# ProPrj_51__2025-02-26.net
KiCad netlist of a schematic drawn in EasyEDA Pro
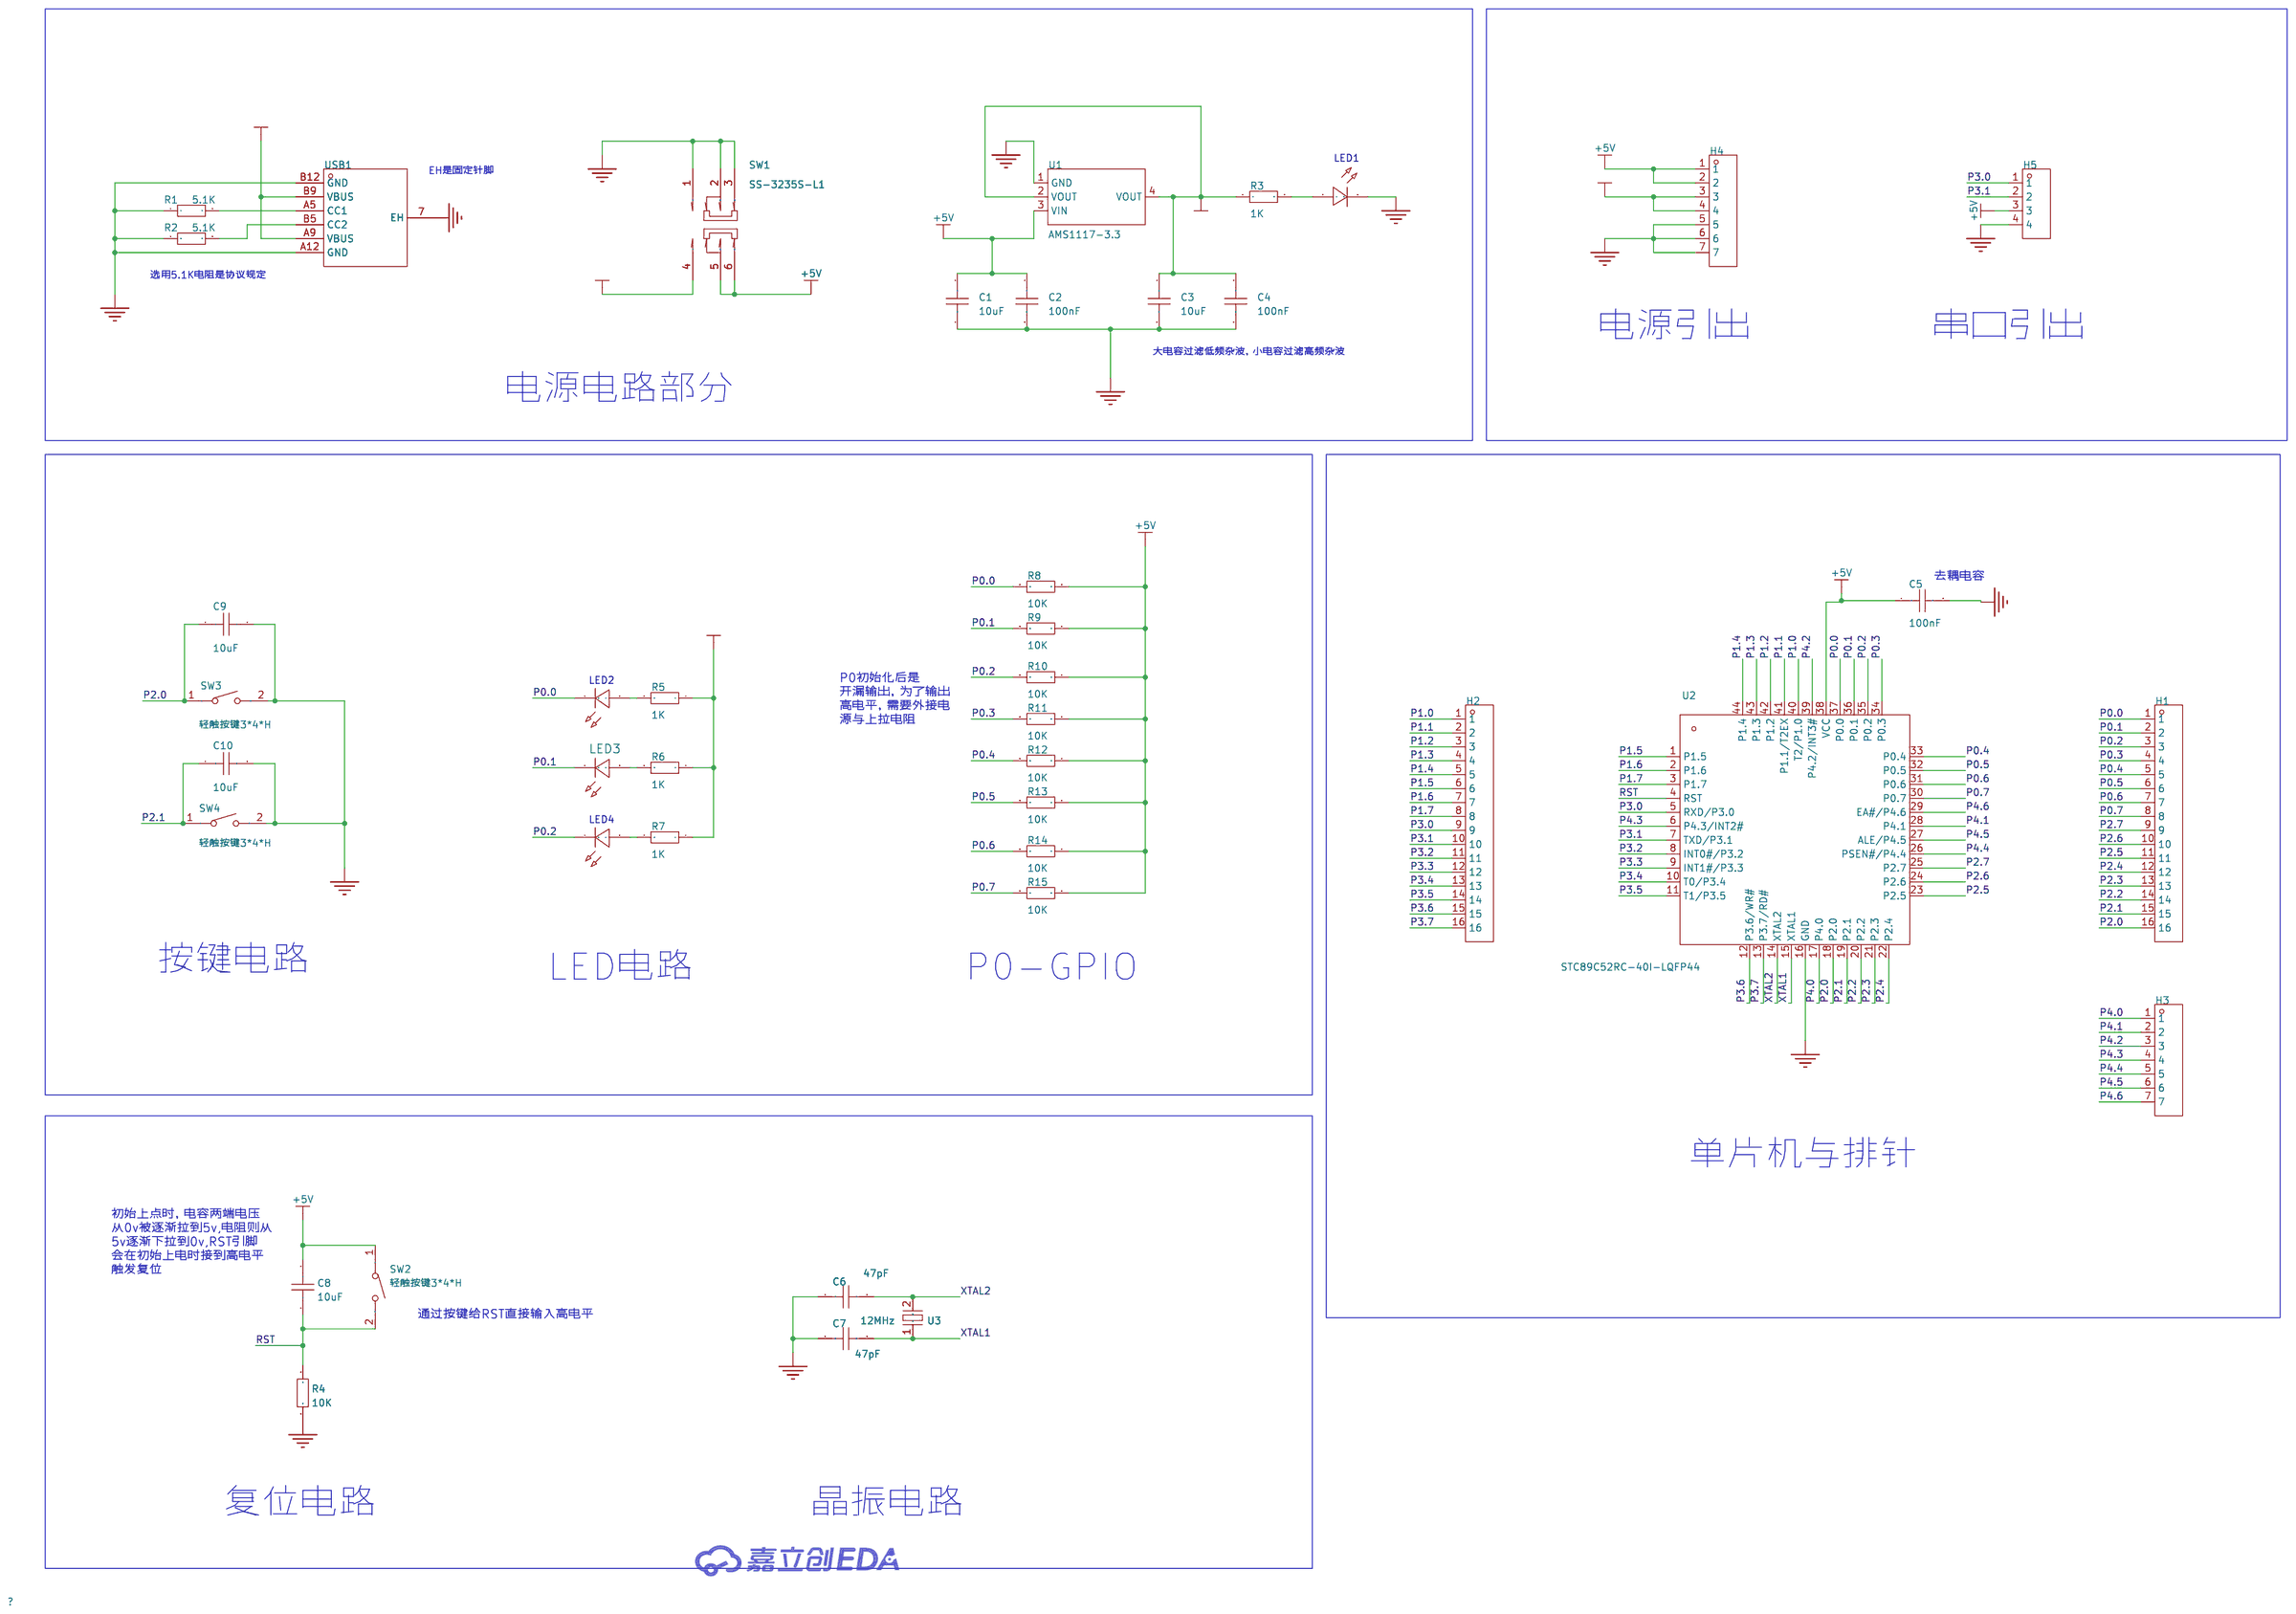
[diagram p0: schematic sheet]

(export (version "E")
  (design (tool "Eeschema 10.0.6"))
  (components
    (comp (ref "C1")
      (value "10uF")
      (footprint "easyedapro:C0805")
      (libsource (lib "easyedapro") (part "CapAcitance"))
    )
    (comp (ref "C2")
      (value "100nF")
      (footprint "easyedapro:C0805")
      (libsource (lib "easyedapro") (part "CapAcitance"))
    )
    (comp (ref "C3")
      (value "10uF")
      (footprint "easyedapro:C0805")
      (libsource (lib "easyedapro") (part "CapAcitance"))
    )
    (comp (ref "C4")
      (value "100nF")
      (footprint "easyedapro:C0805")
      (libsource (lib "easyedapro") (part "CapAcitance"))
    )
    (comp (ref "C5")
      (value "100nF")
      (footprint "easyedapro:C0805")
      (libsource (lib "easyedapro") (part "CapAcitance"))
    )
    (comp (ref "C6")
      (value "47pF")
      (footprint "easyedapro:C0805")
      (libsource (lib "easyedapro") (part "CapAcitance"))
    )
    (comp (ref "C7")
      (value "47pF")
      (footprint "easyedapro:C0805")
      (libsource (lib "easyedapro") (part "CapAcitance"))
    )
    (comp (ref "C8")
      (value "10uF")
      (footprint "easyedapro:C0805")
      (libsource (lib "easyedapro") (part "CapAcitance"))
    )
    (comp (ref "C9")
      (value "10uF")
      (footprint "easyedapro:C0805")
      (libsource (lib "easyedapro") (part "CapAcitance"))
    )
    (comp (ref "C10")
      (value "10uF")
      (footprint "easyedapro:C0805")
      (libsource (lib "easyedapro") (part "CapAcitance"))
    )
    (comp (ref "H1")
      (value "~")
      (footprint "easyedapro:HDR-TH_16P-P2.54-V-M")
      (libsource (lib "easyedapro") (part "HDR_2.54-1x16P"))
    )
    (comp (ref "H2")
      (value "~")
      (footprint "easyedapro:HDR-TH_16P-P2.54-V-M")
      (libsource (lib "easyedapro") (part "HDR_2.54-1x16P"))
    )
    (comp (ref "H3")
      (value "~")
      (footprint "easyedapro:HDR-TH_7P-P2.54-V-M")
      (libsource (lib "easyedapro") (part "PZ254V-11-07P"))
    )
    (comp (ref "H4")
      (value "~")
      (footprint "easyedapro:HDR-TH_7P-P2.54-V-M")
      (libsource (lib "easyedapro") (part "PZ254V-11-07P"))
    )
    (comp (ref "H5")
      (value "~")
      (footprint "easyedapro:HDR-TH_4P-P2.54-V-M")
      (libsource (lib "easyedapro") (part "PZ254V-11-04P"))
    )
    (comp (ref "LED1")
      (value "~")
      (footprint "easyedapro:LED_0805")
      (libsource (lib "easyedapro") (part "LED_G"))
    )
    (comp (ref "LED2")
      (value "~")
      (footprint "easyedapro:LED_0805")
      (libsource (lib "easyedapro") (part "LED_G"))
    )
    (comp (ref "LED3")
      (value "~")
      (footprint "easyedapro:LED_0805")
      (libsource (lib "easyedapro") (part "LED_R"))
    )
    (comp (ref "LED4")
      (value "~")
      (footprint "easyedapro:LED_0805")
      (libsource (lib "easyedapro") (part "LED_B"))
    )
    (comp (ref "R1") (value "5.1K") (footprint "easyedapro:R0805") (libsource (lib "easyedapro") (part "电阻")))
    (comp (ref "R2") (value "5.1K") (footprint "easyedapro:R0805") (libsource (lib "easyedapro") (part "电阻")))
    (comp (ref "R3") (value "1K") (footprint "easyedapro:R0805") (libsource (lib "easyedapro") (part "电阻")))
    (comp (ref "R4") (value "10K") (footprint "easyedapro:R0805") (libsource (lib "easyedapro") (part "电阻")))
    (comp (ref "R5") (value "1K") (footprint "easyedapro:R0805") (libsource (lib "easyedapro") (part "电阻")))
    (comp (ref "R6") (value "1K") (footprint "easyedapro:R0805") (libsource (lib "easyedapro") (part "电阻")))
    (comp (ref "R7") (value "1K") (footprint "easyedapro:R0805") (libsource (lib "easyedapro") (part "电阻")))
    (comp (ref "R8") (value "10K") (footprint "easyedapro:R0805") (libsource (lib "easyedapro") (part "电阻")))
    (comp (ref "R9") (value "10K") (footprint "easyedapro:R0805") (libsource (lib "easyedapro") (part "电阻")))
    (comp (ref "R10") (value "10K") (footprint "easyedapro:R0805") (libsource (lib "easyedapro") (part "电阻")))
    (comp (ref "R11") (value "10K") (footprint "easyedapro:R0805") (libsource (lib "easyedapro") (part "电阻")))
    (comp (ref "R12") (value "10K") (footprint "easyedapro:R0805") (libsource (lib "easyedapro") (part "电阻")))
    (comp (ref "R13") (value "10K") (footprint "easyedapro:R0805") (libsource (lib "easyedapro") (part "电阻")))
    (comp (ref "R14") (value "10K") (footprint "easyedapro:R0805") (libsource (lib "easyedapro") (part "电阻")))
    (comp (ref "R15") (value "10K") (footprint "easyedapro:R0805") (libsource (lib "easyedapro") (part "电阻")))
    (comp (ref "SW1")
      (value "SS-3235S-L1")
      (footprint "easyedapro:SW-SMD_SS-3235S-LX")
      (description "电路结构:双刀双掷;安装方式:卧贴;开关颜色:黑色;额定电流(DC):50mA;额定电压(DC):12V;额定电流(AC):50mA;额定电压(AC):12V;机械寿命:1万次;")
      (fields (field (name "Manufacturer") "XKB Connectivity(中国星坤)"))
      (libsource (lib "easyedapro") (part "SS-3235S-L1"))
    )
    (comp (ref "SW2")
      (value "轻触按键3*4*H")
      (footprint "easyedapro:SW-SMD_L4.0-W2.9-LS5.0")
      (libsource (lib "easyedapro") (part "轻触按键3*4*H"))
    )
    (comp (ref "SW3")
      (value "轻触按键3*4*H")
      (footprint "easyedapro:SW-SMD_L4.0-W2.9-LS5.0")
      (libsource (lib "easyedapro") (part "轻触按键3*4*H"))
    )
    (comp (ref "SW4")
      (value "轻触按键3*4*H")
      (footprint "easyedapro:SW-SMD_L4.0-W2.9-LS5.0")
      (libsource (lib "easyedapro") (part "轻触按键3*4*H"))
    )
    (comp (ref "U1")
      (value "AMS1117-3.3")
      (footprint "easyedapro:SOT-223-3_L6.5-W3.4-P2.30-LS7.0-BR")
      (description "输出类型:固定;工作电压:-;输出电压:3.3V;输出电流:1A;电源纹波抑制比(PSRR):72dB@(120Hz);输出极性:正极;")
      (fields (field (name "Manufacturer") "AMS"))
      (libsource (lib "easyedapro") (part "AMS1117-3.3"))
    )
    (comp (ref "U2")
      (value "STC89C52RC-40I-LQFP44")
      (footprint "easyedapro:LQFP-44_L10.0-W10.0-P0.80-LS12.0-BL")
      (description "CPU内核:51系列;应用领域:-;")
      (fields (field (name "Manufacturer") "STC"))
      (libsource (lib "easyedapro") (part "STC89C52RC-40I_C8707"))
    )
    (comp (ref "U3")
      (value "12MHz")
      (footprint "easyedapro:CRYSTAL-SMD_L11.4-W4.7-LS12.7")
      (description "频率:12MHz;常温频差:±30ppm;外接负载电容:18pF;频率稳定度(全温):±35ppm;")
      (fields
        (field (name "Manufacturer Part") "ABLS-12.000MHZ-B4H-T")
        (field (name "Manufacturer") "ABRACON")
      )
      (libsource (lib "easyedapro") (part "ABLS-12.000MHZ-B4H-T"))
    )
    (comp (ref "USB1")
      (value "TYPE-C-6P-DIP2X2")
      (footprint "easyedapro:TYPE-C-SMD_TYPE-C-6P")
      (libsource (lib "easyedapro") (part "TYPE-C-6P-DIP2X2"))
    )
  )
  (nets
    (net (code "1") (name "+3.3V") (class "Default")
      (node (ref "C3") (pin "1") (pinfunction "1_1") (pintype "input"))
      (node (ref "C4") (pin "1") (pinfunction "1_1") (pintype "input"))
      (node (ref "H4") (pin "3") (pinfunction "3_3") (pintype "unspecified"))
      (node (ref "H4") (pin "4") (pinfunction "4_4") (pintype "unspecified"))
      (node (ref "R3") (pin "1") (pinfunction "1_1") (pintype "input"))
      (node (ref "R5") (pin "1") (pinfunction "1_1") (pintype "input"))
      (node (ref "R6") (pin "1") (pinfunction "1_1") (pintype "input"))
      (node (ref "R7") (pin "1") (pinfunction "1_1") (pintype "input"))
      (node (ref "U1") (pin "2") (pinfunction "VOUT_2") (pintype "unspecified"))
      (node (ref "U1") (pin "4") (pinfunction "VOUT_4") (pintype "unspecified"))
    )
    (net (code "2") (name "+5V") (class "Default")
      (node (ref "C1") (pin "1") (pinfunction "1_1") (pintype "input"))
      (node (ref "C2") (pin "1") (pinfunction "1_1") (pintype "input"))
      (node (ref "C5") (pin "1") (pinfunction "1_1") (pintype "input"))
      (node (ref "C8") (pin "2") (pinfunction "2_2") (pintype "input"))
      (node (ref "H4") (pin "1") (pinfunction "1_1") (pintype "unspecified"))
      (node (ref "H4") (pin "2") (pinfunction "2_2") (pintype "unspecified"))
      (node (ref "H5") (pin "3") (pinfunction "3_3") (pintype "unspecified"))
      (node (ref "R10") (pin "1") (pinfunction "1_1") (pintype "input"))
      (node (ref "R11") (pin "1") (pinfunction "1_1") (pintype "input"))
      (node (ref "R12") (pin "1") (pinfunction "1_1") (pintype "input"))
      (node (ref "R13") (pin "1") (pinfunction "1_1") (pintype "input"))
      (node (ref "R14") (pin "1") (pinfunction "1_1") (pintype "input"))
      (node (ref "R15") (pin "1") (pinfunction "1_1") (pintype "input"))
      (node (ref "R8") (pin "1") (pinfunction "1_1") (pintype "input"))
      (node (ref "R9") (pin "1") (pinfunction "1_1") (pintype "input"))
      (node (ref "SW1") (pin "5") (pinfunction "5_5") (pintype "unspecified"))
      (node (ref "SW1") (pin "6") (pinfunction "6_6") (pintype "unspecified"))
      (node (ref "SW2") (pin "1") (pinfunction "1_1") (pintype "unspecified"))
      (node (ref "U1") (pin "3") (pinfunction "VIN_3") (pintype "unspecified"))
      (node (ref "U2") (pin "38") (pinfunction "VCC_38") (pintype "unspecified"))
    )
    (net (code "3") (name "/P0.0") (class "Default")
      (node (ref "H1") (pin "1") (pinfunction "1_1") (pintype "input"))
      (node (ref "LED2") (pin "1") (pinfunction "C_1") (pintype "input"))
      (node (ref "R8") (pin "2") (pinfunction "2_2") (pintype "input"))
      (node (ref "U2") (pin "37") (pinfunction "P0.0_37") (pintype "unspecified"))
    )
    (net (code "4") (name "/P0.1") (class "Default")
      (node (ref "H1") (pin "2") (pinfunction "2_2") (pintype "input"))
      (node (ref "LED3") (pin "1") (pinfunction "C_1") (pintype "input"))
      (node (ref "R9") (pin "2") (pinfunction "2_2") (pintype "input"))
      (node (ref "U2") (pin "36") (pinfunction "P0.1_36") (pintype "unspecified"))
    )
    (net (code "5") (name "/P0.2") (class "Default")
      (node (ref "H1") (pin "3") (pinfunction "3_3") (pintype "input"))
      (node (ref "LED4") (pin "1") (pinfunction "C_1") (pintype "input"))
      (node (ref "R10") (pin "2") (pinfunction "2_2") (pintype "input"))
      (node (ref "U2") (pin "35") (pinfunction "P0.2_35") (pintype "unspecified"))
    )
    (net (code "6") (name "/P0.3") (class "Default")
      (node (ref "H1") (pin "4") (pinfunction "4_4") (pintype "input"))
      (node (ref "R11") (pin "2") (pinfunction "2_2") (pintype "input"))
      (node (ref "U2") (pin "34") (pinfunction "P0.3_34") (pintype "unspecified"))
    )
    (net (code "7") (name "/P0.4") (class "Default")
      (node (ref "H1") (pin "5") (pinfunction "5_5") (pintype "input"))
      (node (ref "R12") (pin "2") (pinfunction "2_2") (pintype "input"))
      (node (ref "U2") (pin "33") (pinfunction "P0.4_33") (pintype "unspecified"))
    )
    (net (code "8") (name "/P0.5") (class "Default")
      (node (ref "H1") (pin "6") (pinfunction "6_6") (pintype "input"))
      (node (ref "R13") (pin "2") (pinfunction "2_2") (pintype "input"))
      (node (ref "U2") (pin "32") (pinfunction "P0.5_32") (pintype "unspecified"))
    )
    (net (code "9") (name "/P0.6") (class "Default")
      (node (ref "H1") (pin "7") (pinfunction "7_7") (pintype "input"))
      (node (ref "R14") (pin "2") (pinfunction "2_2") (pintype "input"))
      (node (ref "U2") (pin "31") (pinfunction "P0.6_31") (pintype "unspecified"))
    )
    (net (code "10") (name "/P0.7") (class "Default")
      (node (ref "H1") (pin "8") (pinfunction "8_8") (pintype "input"))
      (node (ref "R15") (pin "2") (pinfunction "2_2") (pintype "input"))
      (node (ref "U2") (pin "30") (pinfunction "P0.7_30") (pintype "unspecified"))
    )
    (net (code "11") (name "/P1.0") (class "Default")
      (node (ref "H2") (pin "1") (pinfunction "1_1") (pintype "input"))
      (node (ref "U2") (pin "40") (pinfunction "T2/P1.0_40") (pintype "unspecified"))
    )
    (net (code "12") (name "/P1.1") (class "Default")
      (node (ref "H2") (pin "2") (pinfunction "2_2") (pintype "input"))
      (node (ref "U2") (pin "41") (pinfunction "P1.1/T2EX_41") (pintype "unspecified"))
    )
    (net (code "13") (name "/P1.2") (class "Default")
      (node (ref "H2") (pin "3") (pinfunction "3_3") (pintype "input"))
      (node (ref "U2") (pin "42") (pinfunction "P1.2_42") (pintype "unspecified"))
    )
    (net (code "14") (name "/P1.3") (class "Default")
      (node (ref "H2") (pin "4") (pinfunction "4_4") (pintype "input"))
      (node (ref "U2") (pin "43") (pinfunction "P1.3_43") (pintype "unspecified"))
    )
    (net (code "15") (name "/P1.4") (class "Default")
      (node (ref "H2") (pin "5") (pinfunction "5_5") (pintype "input"))
      (node (ref "U2") (pin "44") (pinfunction "P1.4_44") (pintype "unspecified"))
    )
    (net (code "16") (name "/P1.5") (class "Default")
      (node (ref "H2") (pin "6") (pinfunction "6_6") (pintype "input"))
      (node (ref "U2") (pin "1") (pinfunction "P1.5_1") (pintype "unspecified"))
    )
    (net (code "17") (name "/P1.6") (class "Default")
      (node (ref "H2") (pin "7") (pinfunction "7_7") (pintype "input"))
      (node (ref "U2") (pin "2") (pinfunction "P1.6_2") (pintype "unspecified"))
    )
    (net (code "18") (name "/P1.7") (class "Default")
      (node (ref "H2") (pin "8") (pinfunction "8_8") (pintype "input"))
      (node (ref "U2") (pin "3") (pinfunction "P1.7_3") (pintype "unspecified"))
    )
    (net (code "19") (name "/P2.0") (class "Default")
      (node (ref "C9") (pin "1") (pinfunction "1_1") (pintype "input"))
      (node (ref "H1") (pin "16") (pinfunction "16_16") (pintype "input"))
      (node (ref "SW3") (pin "1") (pinfunction "1_1") (pintype "unspecified"))
      (node (ref "U2") (pin "18") (pinfunction "P2.0_18") (pintype "unspecified"))
    )
    (net (code "20") (name "/P2.1") (class "Default")
      (node (ref "C10") (pin "1") (pinfunction "1_1") (pintype "input"))
      (node (ref "H1") (pin "15") (pinfunction "15_15") (pintype "input"))
      (node (ref "SW4") (pin "1") (pinfunction "1_1") (pintype "unspecified"))
      (node (ref "U2") (pin "19") (pinfunction "P2.1_19") (pintype "unspecified"))
    )
    (net (code "21") (name "/P2.2") (class "Default")
      (node (ref "H1") (pin "14") (pinfunction "14_14") (pintype "input"))
      (node (ref "U2") (pin "20") (pinfunction "P2.2_20") (pintype "unspecified"))
    )
    (net (code "22") (name "/P2.3") (class "Default")
      (node (ref "H1") (pin "13") (pinfunction "13_13") (pintype "input"))
      (node (ref "U2") (pin "21") (pinfunction "P2.3_21") (pintype "unspecified"))
    )
    (net (code "23") (name "/P2.4") (class "Default")
      (node (ref "H1") (pin "12") (pinfunction "12_12") (pintype "input"))
      (node (ref "U2") (pin "22") (pinfunction "P2.4_22") (pintype "unspecified"))
    )
    (net (code "24") (name "/P2.5") (class "Default")
      (node (ref "H1") (pin "11") (pinfunction "11_11") (pintype "input"))
      (node (ref "U2") (pin "23") (pinfunction "P2.5_23") (pintype "unspecified"))
    )
    (net (code "25") (name "/P2.6") (class "Default")
      (node (ref "H1") (pin "10") (pinfunction "10_10") (pintype "input"))
      (node (ref "U2") (pin "24") (pinfunction "P2.6_24") (pintype "unspecified"))
    )
    (net (code "26") (name "/P2.7") (class "Default")
      (node (ref "H1") (pin "9") (pinfunction "9_9") (pintype "input"))
      (node (ref "U2") (pin "25") (pinfunction "P2.7_25") (pintype "unspecified"))
    )
    (net (code "27") (name "/P3.0") (class "Default")
      (node (ref "H2") (pin "9") (pinfunction "9_9") (pintype "input"))
      (node (ref "H5") (pin "1") (pinfunction "1_1") (pintype "unspecified"))
      (node (ref "U2") (pin "5") (pinfunction "RXD/P3.0_5") (pintype "unspecified"))
    )
    (net (code "28") (name "/P3.1") (class "Default")
      (node (ref "H2") (pin "10") (pinfunction "10_10") (pintype "input"))
      (node (ref "H5") (pin "2") (pinfunction "2_2") (pintype "unspecified"))
      (node (ref "U2") (pin "7") (pinfunction "TXD/P3.1_7") (pintype "unspecified"))
    )
    (net (code "29") (name "/P3.2") (class "Default")
      (node (ref "H2") (pin "11") (pinfunction "11_11") (pintype "input"))
      (node (ref "U2") (pin "8") (pinfunction "INT0#/P3.2_8") (pintype "unspecified"))
    )
    (net (code "30") (name "/P3.3") (class "Default")
      (node (ref "H2") (pin "12") (pinfunction "12_12") (pintype "input"))
      (node (ref "U2") (pin "9") (pinfunction "INT1#/P3.3_9") (pintype "unspecified"))
    )
    (net (code "31") (name "/P3.4") (class "Default")
      (node (ref "H2") (pin "13") (pinfunction "13_13") (pintype "input"))
      (node (ref "U2") (pin "10") (pinfunction "T0/P3.4_10") (pintype "unspecified"))
    )
    (net (code "32") (name "/P3.5") (class "Default")
      (node (ref "H2") (pin "14") (pinfunction "14_14") (pintype "input"))
      (node (ref "U2") (pin "11") (pinfunction "T1/P3.5_11") (pintype "unspecified"))
    )
    (net (code "33") (name "/P3.6") (class "Default")
      (node (ref "H2") (pin "15") (pinfunction "15_15") (pintype "input"))
      (node (ref "U2") (pin "12") (pinfunction "P3.6/WR#_12") (pintype "unspecified"))
    )
    (net (code "34") (name "/P3.7") (class "Default")
      (node (ref "H2") (pin "16") (pinfunction "16_16") (pintype "input"))
      (node (ref "U2") (pin "13") (pinfunction "P3.7/RD#_13") (pintype "unspecified"))
    )
    (net (code "35") (name "/P4.0") (class "Default")
      (node (ref "H3") (pin "1") (pinfunction "1_1") (pintype "unspecified"))
      (node (ref "U2") (pin "17") (pinfunction "P4.0_17") (pintype "unspecified"))
    )
    (net (code "36") (name "/P4.1") (class "Default")
      (node (ref "H3") (pin "2") (pinfunction "2_2") (pintype "unspecified"))
      (node (ref "U2") (pin "28") (pinfunction "P4.1_28") (pintype "unspecified"))
    )
    (net (code "37") (name "/P4.2") (class "Default")
      (node (ref "H3") (pin "3") (pinfunction "3_3") (pintype "unspecified"))
      (node (ref "U2") (pin "39") (pinfunction "P4.2/INT3#_39") (pintype "unspecified"))
    )
    (net (code "38") (name "/P4.3") (class "Default")
      (node (ref "H3") (pin "4") (pinfunction "4_4") (pintype "unspecified"))
      (node (ref "U2") (pin "6") (pinfunction "P4.3/INT2#_6") (pintype "unspecified"))
    )
    (net (code "39") (name "/P4.4") (class "Default")
      (node (ref "H3") (pin "5") (pinfunction "5_5") (pintype "unspecified"))
      (node (ref "U2") (pin "26") (pinfunction "PSEN#/P4.4_26") (pintype "unspecified"))
    )
    (net (code "40") (name "/P4.5") (class "Default")
      (node (ref "H3") (pin "6") (pinfunction "6_6") (pintype "unspecified"))
      (node (ref "U2") (pin "27") (pinfunction "ALE/P4.5_27") (pintype "unspecified"))
    )
    (net (code "41") (name "/P4.6") (class "Default")
      (node (ref "H3") (pin "7") (pinfunction "7_7") (pintype "unspecified"))
      (node (ref "U2") (pin "29") (pinfunction "EA#/P4.6_29") (pintype "unspecified"))
    )
    (net (code "42") (name "/RST") (class "Default")
      (node (ref "C8") (pin "1") (pinfunction "1_1") (pintype "input"))
      (node (ref "R4") (pin "2") (pinfunction "2_2") (pintype "input"))
      (node (ref "SW2") (pin "2") (pinfunction "2_2") (pintype "unspecified"))
      (node (ref "U2") (pin "4") (pinfunction "RST_4") (pintype "unspecified"))
    )
    (net (code "43") (name "/XTAL1") (class "Default")
      (node (ref "C7") (pin "2") (pinfunction "2_2") (pintype "input"))
      (node (ref "U2") (pin "15") (pinfunction "XTAL1_15") (pintype "unspecified"))
      (node (ref "U3") (pin "1") (pinfunction "1_1") (pintype "input"))
    )
    (net (code "44") (name "/XTAL2") (class "Default")
      (node (ref "C6") (pin "2") (pinfunction "2_2") (pintype "input"))
      (node (ref "U2") (pin "14") (pinfunction "XTAL2_14") (pintype "unspecified"))
      (node (ref "U3") (pin "2") (pinfunction "GND_2") (pintype "input"))
    )
    (net (code "45") (name "GND") (class "Default")
      (node (ref "C1") (pin "2") (pinfunction "2_2") (pintype "input"))
      (node (ref "C10") (pin "2") (pinfunction "2_2") (pintype "input"))
      (node (ref "C2") (pin "2") (pinfunction "2_2") (pintype "input"))
      (node (ref "C3") (pin "2") (pinfunction "2_2") (pintype "input"))
      (node (ref "C4") (pin "2") (pinfunction "2_2") (pintype "input"))
      (node (ref "C5") (pin "2") (pinfunction "2_2") (pintype "input"))
      (node (ref "C6") (pin "1") (pinfunction "1_1") (pintype "input"))
      (node (ref "C7") (pin "1") (pinfunction "1_1") (pintype "input"))
      (node (ref "C9") (pin "2") (pinfunction "2_2") (pintype "input"))
      (node (ref "H4") (pin "5") (pinfunction "5_5") (pintype "unspecified"))
      (node (ref "H4") (pin "6") (pinfunction "6_6") (pintype "unspecified"))
      (node (ref "H4") (pin "7") (pinfunction "7_7") (pintype "unspecified"))
      (node (ref "H5") (pin "4") (pinfunction "4_4") (pintype "unspecified"))
      (node (ref "LED1") (pin "1") (pinfunction "C_1") (pintype "input"))
      (node (ref "R1") (pin "1") (pinfunction "1_1") (pintype "input"))
      (node (ref "R2") (pin "1") (pinfunction "1_1") (pintype "input"))
      (node (ref "R4") (pin "1") (pinfunction "1_1") (pintype "input"))
      (node (ref "SW1") (pin "1") (pinfunction "1_1") (pintype "unspecified"))
      (node (ref "SW1") (pin "2") (pinfunction "2_2") (pintype "unspecified"))
      (node (ref "SW1") (pin "3") (pinfunction "3_3") (pintype "unspecified"))
      (node (ref "SW3") (pin "2") (pinfunction "2_2") (pintype "unspecified"))
      (node (ref "SW4") (pin "2") (pinfunction "2_2") (pintype "unspecified"))
      (node (ref "U1") (pin "1") (pinfunction "GND_1") (pintype "unspecified"))
      (node (ref "U2") (pin "16") (pinfunction "GND_16") (pintype "unspecified"))
      (node (ref "USB1") (pin "7") (pinfunction "EH_7") (pintype "unspecified"))
      (node (ref "USB1") (pin "A12") (pinfunction "GND_A12") (pintype "unspecified"))
      (node (ref "USB1") (pin "B12") (pinfunction "GND_B12") (pintype "unspecified"))
    )
    (net (code "46") (name "Net-(LED1-A)") (class "Default")
      (node (ref "LED1") (pin "2") (pinfunction "A_2") (pintype "input"))
      (node (ref "R3") (pin "2") (pinfunction "2_2") (pintype "input"))
    )
    (net (code "47") (name "Net-(LED2-A)") (class "Default")
      (node (ref "LED2") (pin "2") (pinfunction "A_2") (pintype "input"))
      (node (ref "R5") (pin "2") (pinfunction "2_2") (pintype "input"))
    )
    (net (code "48") (name "Net-(LED3-A)") (class "Default")
      (node (ref "LED3") (pin "2") (pinfunction "A_2") (pintype "input"))
      (node (ref "R6") (pin "2") (pinfunction "2_2") (pintype "input"))
    )
    (net (code "49") (name "Net-(LED4-A)") (class "Default")
      (node (ref "LED4") (pin "2") (pinfunction "A_2") (pintype "input"))
      (node (ref "R7") (pin "2") (pinfunction "2_2") (pintype "input"))
    )
    (net (code "50") (name "Net-(USB1-CC1)") (class "Default")
      (node (ref "R1") (pin "2") (pinfunction "2_2") (pintype "input"))
      (node (ref "USB1") (pin "A5") (pinfunction "CC1_A5") (pintype "unspecified"))
    )
    (net (code "51") (name "Net-(USB1-CC2)") (class "Default")
      (node (ref "R2") (pin "2") (pinfunction "2_2") (pintype "input"))
      (node (ref "USB1") (pin "B5") (pinfunction "CC2_B5") (pintype "unspecified"))
    )
    (net (code "52") (name "VCC+5V") (class "Default")
      (node (ref "SW1") (pin "4") (pinfunction "4_4") (pintype "unspecified"))
      (node (ref "USB1") (pin "A9") (pinfunction "VBUS_A9") (pintype "unspecified"))
      (node (ref "USB1") (pin "B9") (pinfunction "VBUS_B9") (pintype "unspecified"))
    )
  )
)
